# CP2102N_SCH.net
KiCad netlist of a schematic drawn in Altium Designer
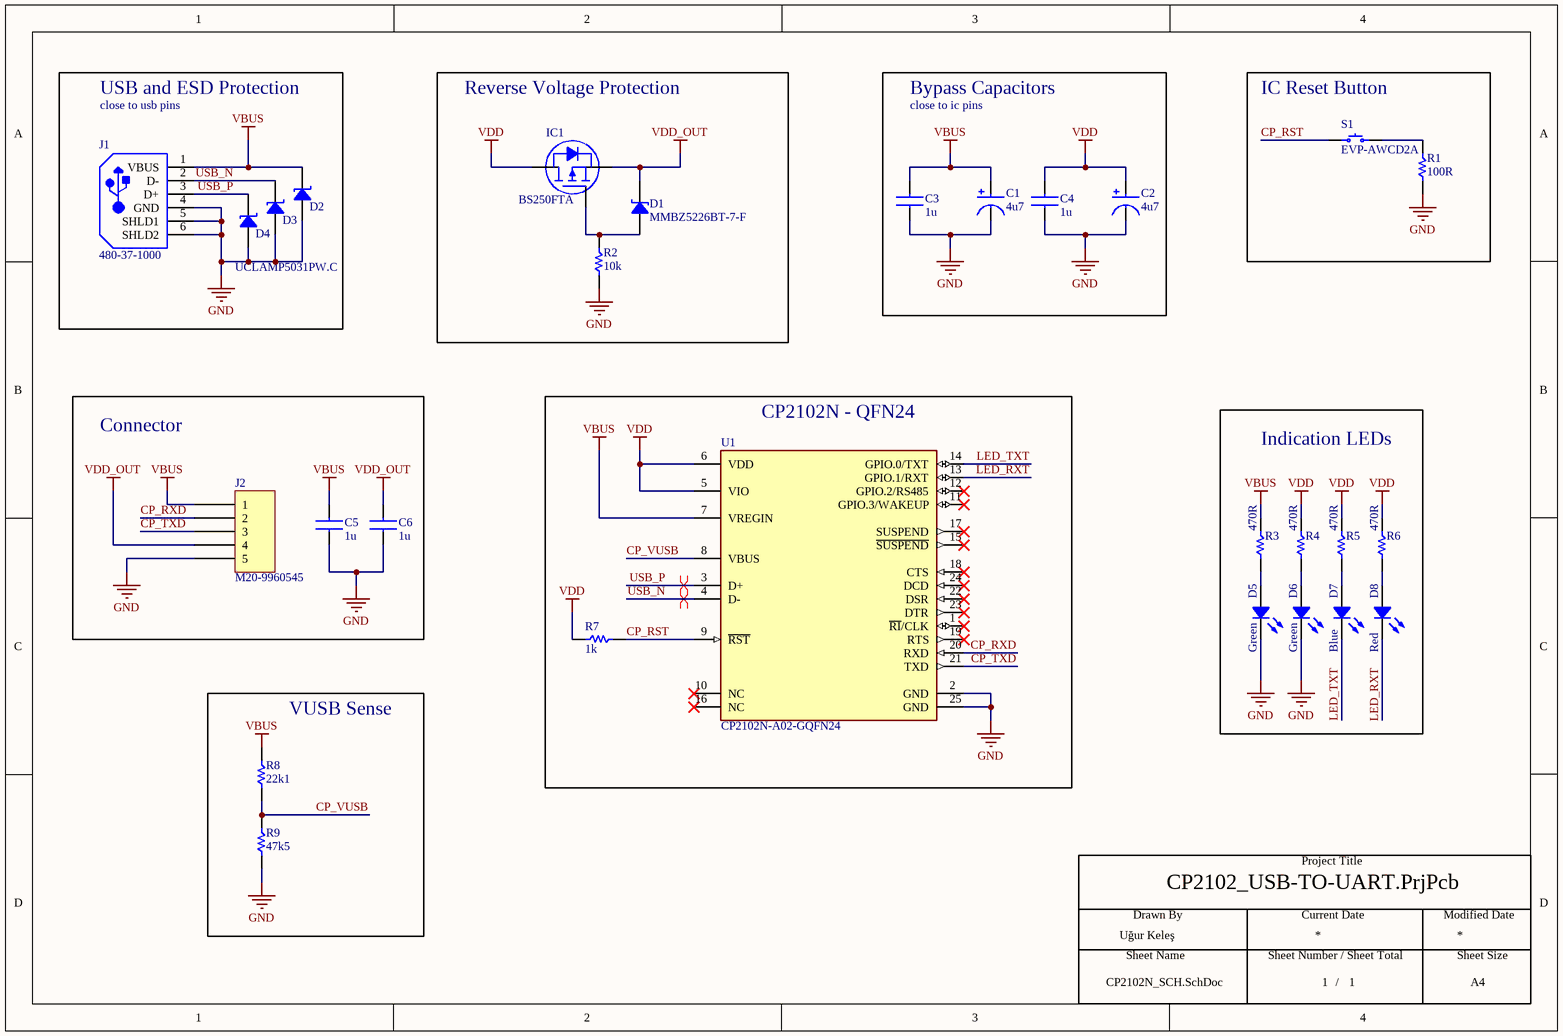
[diagram p0: CP2102N_SCH.SchDoc]

(export (version "E")
  (design (tool "Eeschema 10.0.6"))
  (components
    (comp (ref "C1")
      (value "4u7")
      (footprint "CAP TANT 0805")
      (fields (field (name "DESIGNED BY") "UK"))
      (libsource (lib "UKLIB") (part "CAP TANT GENERIC 0805"))
    )
    (comp (ref "C2")
      (value "4u7")
      (footprint "CAP TANT 0805")
      (fields (field (name "DESIGNED BY") "UK"))
      (libsource (lib "UKLIB") (part "CAP TANT GENERIC 0805"))
    )
    (comp (ref "C3")
      (value "1u")
      (footprint "CAP CER 0402")
      (fields (field (name "DESIGNED BY") "UK"))
      (libsource (lib "UKLIB") (part "CAP CER GENERIC 0402"))
    )
    (comp (ref "C4")
      (value "1u")
      (footprint "CAP CER 0402")
      (fields (field (name "DESIGNED BY") "UK"))
      (libsource (lib "UKLIB") (part "CAP CER GENERIC 0402"))
    )
    (comp (ref "C5")
      (value "1u")
      (footprint "CAP CER 0402")
      (fields (field (name "DESIGNED BY") "UK"))
      (libsource (lib "UKLIB") (part "CAP CER GENERIC 0402"))
    )
    (comp (ref "C6")
      (value "1u")
      (footprint "CAP CER 0402")
      (fields (field (name "DESIGNED BY") "UK"))
      (libsource (lib "UKLIB") (part "CAP CER GENERIC 0402"))
    )
    (comp (ref "D1")
      (value "MMBZ5226BT-7-F")
      (footprint "DIODES SOT-523")
      (description "DIODE ZENER 3.3V 150MW SOT523")
      (fields (field (name "MANUFACTURER") "Diodes Incorporated") (field (name "TOLERANCE") "±5%"))
      (libsource (lib "Celestial Altium Library - altium_library") (part "Diode Zener"))
    )
    (comp (ref "D2")
      (value "UCLAMP5031PW.C")
      (footprint "0402")
      (description "5V ESD & EOS PROTECTION")
      (fields (field (name "MANUFACTURER") "Semtech Corporation"))
      (libsource (lib "Celestial Altium Library - altium_library") (part "DIODE TVS UNI"))
    )
    (comp (ref "D3")
      (value "UCLAMP5031PW.C")
      (footprint "0402")
      (description "5V ESD & EOS PROTECTION")
      (fields (field (name "MANUFACTURER") "Semtech Corporation"))
      (libsource (lib "Celestial Altium Library - altium_library") (part "DIODE TVS UNI"))
    )
    (comp (ref "D4")
      (value "UCLAMP5031PW.C")
      (footprint "0402")
      (description "5V ESD & EOS PROTECTION")
      (fields (field (name "MANUFACTURER") "Semtech Corporation"))
      (libsource (lib "Celestial Altium Library - altium_library") (part "DIODE TVS UNI"))
    )
    (comp (ref "D5")
      (value "Green")
      (footprint "LED 0402_1005 GREEN")
      (description "LED GREEN CLEAR 0402 SMD")
      (fields (field (name "PART NUMBER") "QBLP595-AG15") (field (name "MANUFACTURER") "QT Brightek (QTB)"))
      (libsource (lib "Celestial Altium Library - altium_library") (part "LED"))
    )
    (comp (ref "D6")
      (value "Green")
      (footprint "LED 0402_1005 GREEN")
      (description "LED GREEN CLEAR 0402 SMD")
      (fields (field (name "PART NUMBER") "QBLP595-AG15") (field (name "MANUFACTURER") "QT Brightek (QTB)"))
      (libsource (lib "Celestial Altium Library - altium_library") (part "LED"))
    )
    (comp (ref "D7")
      (value "Blue")
      (footprint "LED 0402_1005 BLUE")
      (description "LED BLUE CLEAR 0402 SMD")
      (fields (field (name "PART NUMBER") "QBLP595-IB5") (field (name "MANUFACTURER") "QT Brightek (QTB)"))
      (libsource (lib "Celestial Altium Library - altium_library") (part "LED"))
    )
    (comp (ref "D8")
      (value "Red")
      (footprint "LED 0402_1005 RED")
      (description "LED RED CLEAR 0402 SMD")
      (fields
        (field (name "PART NUMBER") "QBLP595-R5-2897")
        (field (name "MANUFACTURER") "QT Brightek (QTB)")
      )
      (libsource (lib "Celestial Altium Library - altium_library") (part "LED"))
    )
    (comp (ref "IC1")
      (value "BS250FTA")
      (footprint "DIODES SOT-23-3")
      (description "MOSFET P-CH 45V 90MA SOT23-3")
      (fields (field (name "MANUFACTURER") "Diodes Incorporated"))
      (libsource (lib "Celestial Altium Library - altium_library") (part "DIODES MOSFET P-CH SOT-23-3"))
    )
    (comp (ref "J1")
      (value "480-37-1000")
      (footprint "MOLX-480-37-1000_V")
      (fields (field (name "TOLERANCE") "1%"))
      (libsource (lib "Altium Content Vault") (part "USB-4-2SHLD"))
    )
    (comp (ref "J2")
      (value "M20-9960545")
      (footprint "HARWIN M20-9960545")
      (description "CONN HEADER R/A 5POS 2.54MM")
      (fields (field (name "MANUFACTURER") "Harwin Inc."))
      (libsource (lib "Celestial Altium Library - altium_library") (part "5 Pin"))
    )
    (comp (ref "R1")
      (value "100R")
      (footprint "Resistor 0402")
      (description "SMD Chip Resistor, 0402 [1005 Metric], Thick Film, General Purpose")
      (fields (field (name "DESIGNED BY") "UK"))
      (libsource (lib "UKLIB") (part "RES 0402"))
    )
    (comp (ref "R2")
      (value "10k")
      (footprint "Resistor 0402")
      (description "SMD Chip Resistor, 0402 [1005 Metric], Thick Film, General Purpose")
      (fields (field (name "DESIGNED BY") "UK"))
      (libsource (lib "UKLIB") (part "RES 0402"))
    )
    (comp (ref "R3")
      (value "470R")
      (footprint "Resistor 0402")
      (description "SMD Chip Resistor, 0402 [1005 Metric], Thick Film, General Purpose")
      (fields (field (name "DESIGNED BY") "UK"))
      (libsource (lib "UKLIB") (part "RES 0402"))
    )
    (comp (ref "R4")
      (value "470R")
      (footprint "Resistor 0402")
      (description "SMD Chip Resistor, 0402 [1005 Metric], Thick Film, General Purpose")
      (fields (field (name "DESIGNED BY") "UK"))
      (libsource (lib "UKLIB") (part "RES 0402"))
    )
    (comp (ref "R5")
      (value "470R")
      (footprint "Resistor 0402")
      (description "SMD Chip Resistor, 0402 [1005 Metric], Thick Film, General Purpose")
      (fields (field (name "DESIGNED BY") "UK"))
      (libsource (lib "UKLIB") (part "RES 0402"))
    )
    (comp (ref "R6")
      (value "470R")
      (footprint "Resistor 0402")
      (description "SMD Chip Resistor, 0402 [1005 Metric], Thick Film, General Purpose")
      (fields (field (name "DESIGNED BY") "UK"))
      (libsource (lib "UKLIB") (part "RES 0402"))
    )
    (comp (ref "R7")
      (value "1k")
      (footprint "Resistor 0402")
      (description "SMD Chip Resistor, 0402 [1005 Metric], Thick Film, General Purpose")
      (fields (field (name "DESIGNED BY") "UK"))
      (libsource (lib "UKLIB") (part "RES 0402"))
    )
    (comp (ref "R8")
      (value "22k1")
      (footprint "Resistor 0402")
      (description "SMD Chip Resistor, 0402 [1005 Metric], Thick Film, General Purpose")
      (fields (field (name "DESIGNED BY") "UK"))
      (libsource (lib "UKLIB") (part "RES 0402"))
    )
    (comp (ref "R9")
      (value "47k5")
      (footprint "Resistor 0402")
      (description "SMD Chip Resistor, 0402 [1005 Metric], Thick Film, General Purpose")
      (fields (field (name "DESIGNED BY") "UK"))
      (libsource (lib "UKLIB") (part "RES 0402"))
    )
    (comp (ref "S1")
      (value "EVP-AWCD2A")
      (footprint "PANASONIC EVPAW")
      (description "SWITCH TACTILE SPST-NO 0.02A 15V")
      (fields (field (name "MANUFACTURER") "Panasonic Electronic Components"))
      (libsource (lib "Celestial Altium Library - altium_library") (part "SPST-NO 2 PIN"))
    )
    (comp (ref "U1")
      (value "CP2102N-A02-GQFN24")
      (footprint "FP-CP2102N-A02-GQFN24-MFG")
      (description "IC USB TO UART BRIDGE QFN24")
      (libsource (lib "Altium Content Vault") (part "132705adcabca70c0fc25feb25b66a0"))
    )
  )
  (nets
    (net (code "1") (name "/CP_RST") (class "Default")
      (node (ref "R7") (pin "2") (pinfunction "2_2") (pintype "passive"))
      (node (ref "S1") (pin "1") (pinfunction "1_1") (pintype "passive"))
      (node (ref "U1") (pin "9") (pinfunction "~{RST}_9") (pintype "input"))
    )
    (net (code "2") (name "/CP_RXD") (class "Default")
      (node (ref "J2") (pin "2") (pinfunction "2_2") (pintype "passive"))
      (node (ref "U1") (pin "20") (pinfunction "RXD_20") (pintype "input"))
    )
    (net (code "3") (name "/CP_TXD") (class "Default")
      (node (ref "J2") (pin "3") (pinfunction "3_3") (pintype "passive"))
      (node (ref "U1") (pin "21") (pinfunction "TXD_21") (pintype "output"))
    )
    (net (code "4") (name "/CP_VUSB") (class "Default")
      (node (ref "R8") (pin "1") (pinfunction "1_1") (pintype "passive"))
      (node (ref "R9") (pin "2") (pinfunction "2_2") (pintype "passive"))
      (node (ref "U1") (pin "8") (pinfunction "VBUS_8") (pintype "power_in"))
    )
    (net (code "5") (name "/LED_RXT") (class "Default")
      (node (ref "D8") (pin "2") (pinfunction "2_2") (pintype "passive"))
      (node (ref "U1") (pin "13") (pinfunction "GPIO.1/RXT_13") (pintype "bidirectional"))
    )
    (net (code "6") (name "/LED_TXT") (class "Default")
      (node (ref "D7") (pin "2") (pinfunction "2_2") (pintype "passive"))
      (node (ref "U1") (pin "14") (pinfunction "GPIO.0/TXT_14") (pintype "bidirectional"))
    )
    (net (code "7") (name "/USB_N") (class "Default")
      (node (ref "D3") (pin "2") (pinfunction "2_2") (pintype "passive"))
      (node (ref "J1") (pin "2") (pinfunction "D-_2") (pintype "passive"))
      (node (ref "U1") (pin "4") (pinfunction "D-_4") (pintype "passive"))
    )
    (net (code "8") (name "/USB_P") (class "Default")
      (node (ref "D4") (pin "2") (pinfunction "2_2") (pintype "passive"))
      (node (ref "J1") (pin "3") (pinfunction "D+_3") (pintype "passive"))
      (node (ref "U1") (pin "3") (pinfunction "D+_3") (pintype "passive"))
    )
    (net (code "9") (name "GND") (class "Default")
      (node (ref "C1") (pin "2") (pinfunction "2_2") (pintype "passive"))
      (node (ref "C2") (pin "2") (pinfunction "2_2") (pintype "passive"))
      (node (ref "C3") (pin "1") (pinfunction "1_1") (pintype "passive"))
      (node (ref "C4") (pin "1") (pinfunction "1_1") (pintype "passive"))
      (node (ref "C5") (pin "1") (pinfunction "1_1") (pintype "passive"))
      (node (ref "C6") (pin "1") (pinfunction "1_1") (pintype "passive"))
      (node (ref "D2") (pin "1") (pinfunction "1_1") (pintype "passive"))
      (node (ref "D3") (pin "1") (pinfunction "1_1") (pintype "passive"))
      (node (ref "D4") (pin "1") (pinfunction "1_1") (pintype "passive"))
      (node (ref "D5") (pin "2") (pinfunction "2_2") (pintype "passive"))
      (node (ref "D6") (pin "2") (pinfunction "2_2") (pintype "passive"))
      (node (ref "J1") (pin "4") (pinfunction "GND_4") (pintype "passive"))
      (node (ref "J1") (pin "5") (pinfunction "SHLD1_5") (pintype "passive"))
      (node (ref "J1") (pin "6") (pinfunction "SHLD2_6") (pintype "passive"))
      (node (ref "J2") (pin "5") (pinfunction "5_5") (pintype "passive"))
      (node (ref "R1") (pin "1") (pinfunction "1_1") (pintype "passive"))
      (node (ref "R2") (pin "1") (pinfunction "1_1") (pintype "passive"))
      (node (ref "R9") (pin "1") (pinfunction "1_1") (pintype "passive"))
      (node (ref "U1") (pin "2") (pinfunction "GND_2") (pintype "power_in"))
      (node (ref "U1") (pin "25") (pinfunction "GND_25") (pintype "power_in"))
    )
    (net (code "10") (name "Net-(D5-Pad1)") (class "Default")
      (node (ref "D5") (pin "1") (pinfunction "1_1") (pintype "passive"))
      (node (ref "R3") (pin "1") (pinfunction "1_1") (pintype "passive"))
    )
    (net (code "11") (name "Net-(D6-Pad1)") (class "Default")
      (node (ref "D6") (pin "1") (pinfunction "1_1") (pintype "passive"))
      (node (ref "R4") (pin "1") (pinfunction "1_1") (pintype "passive"))
    )
    (net (code "12") (name "Net-(D7-Pad1)") (class "Default")
      (node (ref "D7") (pin "1") (pinfunction "1_1") (pintype "passive"))
      (node (ref "R5") (pin "1") (pinfunction "1_1") (pintype "passive"))
    )
    (net (code "13") (name "Net-(D8-Pad1)") (class "Default")
      (node (ref "D8") (pin "1") (pinfunction "1_1") (pintype "passive"))
      (node (ref "R6") (pin "1") (pinfunction "1_1") (pintype "passive"))
    )
    (net (code "14") (name "Net-(IC1-G)") (class "Default")
      (node (ref "D1") (pin "1") (pinfunction "1_1") (pintype "passive"))
      (node (ref "IC1") (pin "1") (pinfunction "G_1") (pintype "passive"))
      (node (ref "R2") (pin "2") (pinfunction "2_2") (pintype "passive"))
    )
    (net (code "15") (name "Net-(R1-Pad2)") (class "Default")
      (node (ref "R1") (pin "2") (pinfunction "2_2") (pintype "passive"))
      (node (ref "S1") (pin "2") (pinfunction "2_2") (pintype "passive"))
    )
    (net (code "16") (name "VBUS") (class "Default")
      (node (ref "C1") (pin "1") (pinfunction "1_1") (pintype "passive"))
      (node (ref "C3") (pin "2") (pinfunction "2_2") (pintype "passive"))
      (node (ref "C5") (pin "2") (pinfunction "2_2") (pintype "passive"))
      (node (ref "D2") (pin "2") (pinfunction "2_2") (pintype "passive"))
      (node (ref "J1") (pin "1") (pinfunction "VBUS_1") (pintype "passive"))
      (node (ref "J2") (pin "1") (pinfunction "1_1") (pintype "passive"))
      (node (ref "R3") (pin "2") (pinfunction "2_2") (pintype "passive"))
      (node (ref "R8") (pin "2") (pinfunction "2_2") (pintype "passive"))
      (node (ref "U1") (pin "7") (pinfunction "VREGIN_7") (pintype "power_in"))
    )
    (net (code "17") (name "VDD") (class "Default")
      (node (ref "C2") (pin "1") (pinfunction "1_1") (pintype "passive"))
      (node (ref "C4") (pin "2") (pinfunction "2_2") (pintype "passive"))
      (node (ref "IC1") (pin "3") (pinfunction "D_3") (pintype "passive"))
      (node (ref "R4") (pin "2") (pinfunction "2_2") (pintype "passive"))
      (node (ref "R5") (pin "2") (pinfunction "2_2") (pintype "passive"))
      (node (ref "R6") (pin "2") (pinfunction "2_2") (pintype "passive"))
      (node (ref "R7") (pin "1") (pinfunction "1_1") (pintype "passive"))
      (node (ref "U1") (pin "5") (pinfunction "VIO_5") (pintype "power_in"))
      (node (ref "U1") (pin "6") (pinfunction "VDD_6") (pintype "power_in"))
    )
    (net (code "18") (name "VDD_OUT") (class "Default")
      (node (ref "C6") (pin "2") (pinfunction "2_2") (pintype "passive"))
      (node (ref "D1") (pin "2") (pinfunction "2_2") (pintype "passive"))
      (node (ref "IC1") (pin "2") (pinfunction "S_2") (pintype "passive"))
      (node (ref "J2") (pin "4") (pinfunction "4_4") (pintype "passive"))
    )
    (net (code "19") (name "unconnected-(U1-CTS-Pad18)") (class "Default")
      (node (ref "U1") (pin "18") (pinfunction "CTS_18") (pintype "input+no_connect"))
    )
    (net (code "20") (name "unconnected-(U1-DCD-Pad24)") (class "Default")
      (node (ref "U1") (pin "24") (pinfunction "DCD_24") (pintype "input+no_connect"))
    )
    (net (code "21") (name "unconnected-(U1-DSR-Pad22)") (class "Default")
      (node (ref "U1") (pin "22") (pinfunction "DSR_22") (pintype "input+no_connect"))
    )
    (net (code "22") (name "unconnected-(U1-DTR-Pad23)") (class "Default")
      (node (ref "U1") (pin "23") (pinfunction "DTR_23") (pintype "output+no_connect"))
    )
    (net (code "23") (name "unconnected-(U1-GPIO.2{slash}RS485-Pad12)") (class "Default")
      (node (ref "U1") (pin "12") (pinfunction "GPIO.2/RS485_12") (pintype "bidirectional+no_connect"))
    )
    (net (code "24") (name "unconnected-(U1-GPIO.3{slash}WAKEUP-Pad11)") (class "Default")
      (node (ref "U1") (pin "11") (pinfunction "GPIO.3/WAKEUP_11") (pintype "bidirectional+no_connect"))
    )
    (net (code "25") (name "unconnected-(U1-NC-Pad10)") (class "Default")
      (node (ref "U1") (pin "10") (pinfunction "NC_10") (pintype "passive+no_connect"))
    )
    (net (code "26") (name "unconnected-(U1-NC-Pad16)") (class "Default")
      (node (ref "U1") (pin "16") (pinfunction "NC_16") (pintype "passive+no_connect"))
    )
    (net (code "27") (name "unconnected-(U1-RTS-Pad19)") (class "Default")
      (node (ref "U1") (pin "19") (pinfunction "RTS_19") (pintype "output+no_connect"))
    )
    (net (code "28") (name "unconnected-(U1-SUSPEND-Pad17)") (class "Default")
      (node (ref "U1") (pin "17") (pinfunction "SUSPEND_17") (pintype "output+no_connect"))
    )
    (net (code "29") (name "unconnected-(U1-~{RI}{slash}CLK-Pad1)") (class "Default")
      (node (ref "U1") (pin "1") (pinfunction "~{RI}/CLK_1") (pintype "bidirectional+no_connect"))
    )
    (net (code "30") (name "unconnected-(U1-~{SUSPEND}-Pad15)") (class "Default")
      (node (ref "U1") (pin "15") (pinfunction "~{SUSPEND}_15") (pintype "output+no_connect"))
    )
  )
)
